# INPUT_Module.net
KiCad netlist of a schematic drawn in Altium Designer
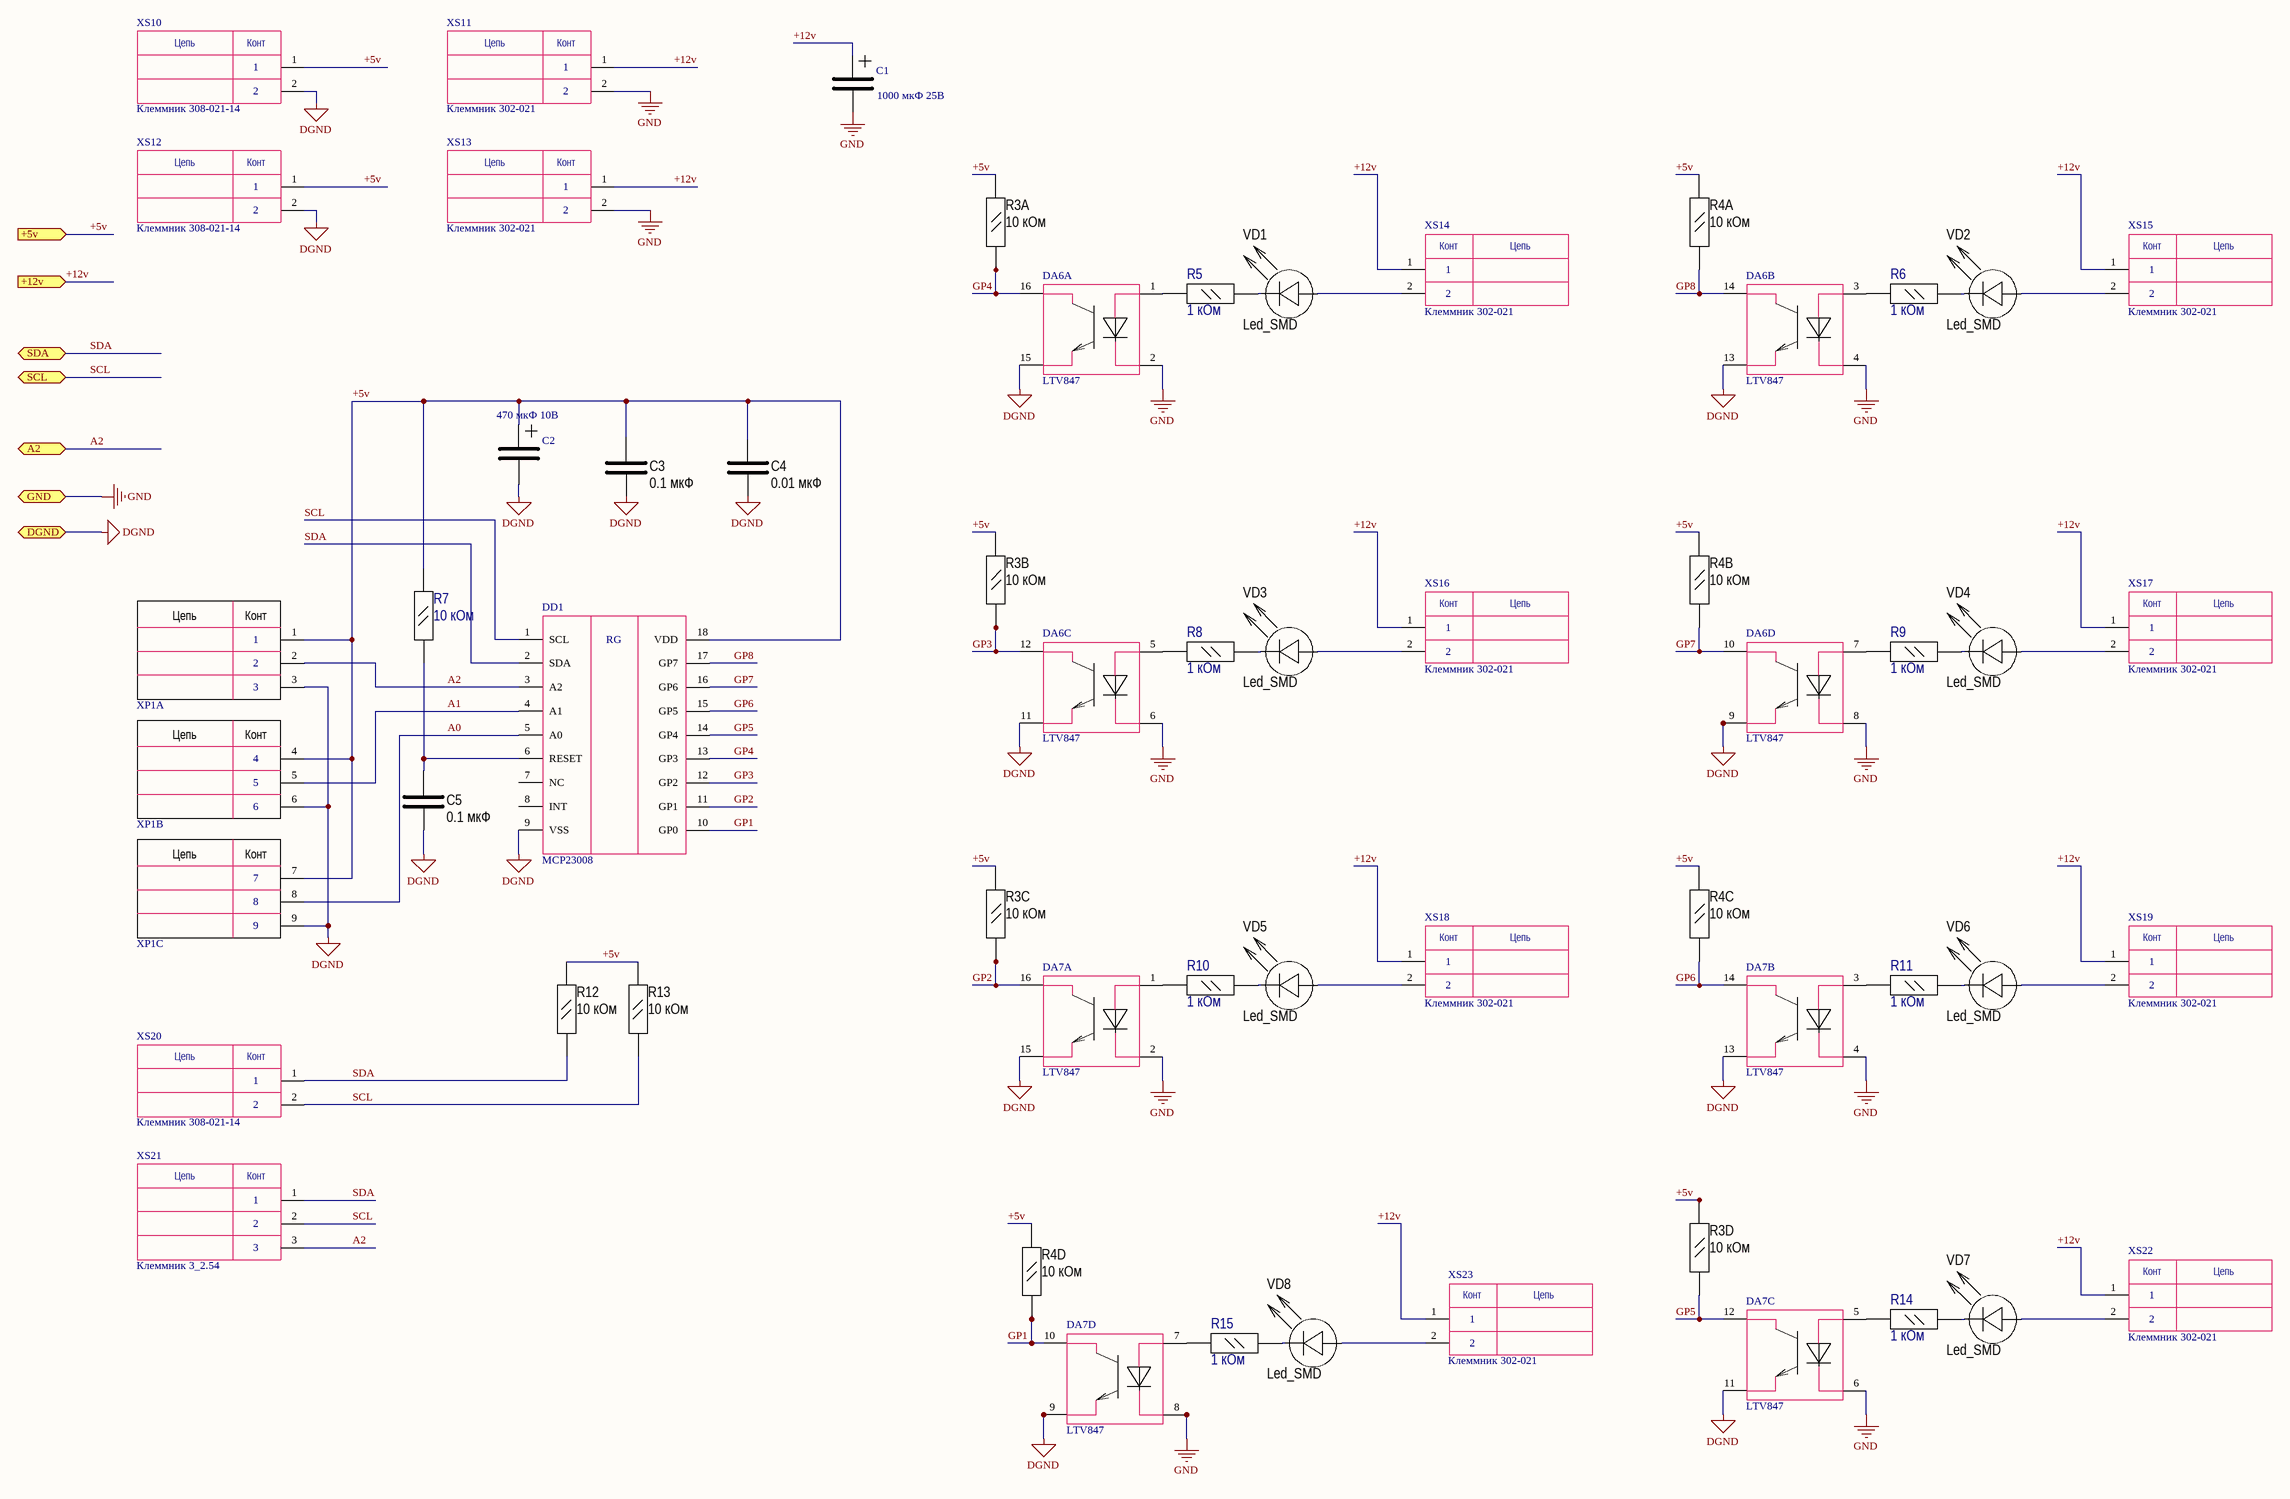
[diagram p0: INPUT_Module.SchDoc]

(export (version "E")
  (design (tool "Eeschema 10.0.6"))
  (components
    (comp (ref "C1")
      (value "1000 мкФ 25В")
      (footprint "K50-35_10mm")
      (libsource (lib "Capicator") (part "K50-35_10mm"))
    )
    (comp (ref "C2")
      (value "470 мкФ 10В")
      (footprint "K50-35_6.3mm")
      (libsource (lib "Capicator") (part "K50-35_6.3mm"))
    )
    (comp (ref "C3") (value "0.1 мкФ") (footprint "C0603") (libsource (lib "Capicator") (part "Cap_SMD")))
    (comp (ref "C4") (value "0.01 мкФ") (footprint "C0603") (libsource (lib "Capicator") (part "C0603")))
    (comp (ref "C5") (value "0.1 мкФ") (footprint "C0603") (libsource (lib "Capicator") (part "Cap_SMD")))
    (comp (ref "DA6") (value "LTV847") (footprint "DIP16") (libsource (lib "OptoRelay") (part "LTV847")))
    (comp (ref "DA7") (value "LTV847") (footprint "DIP16") (libsource (lib "OptoRelay") (part "LTV847")))
    (comp (ref "DD1")
      (value "MCP23008")
      (footprint "SOIC18")
      (libsource (lib "Микросхемы импортные") (part "MCP23008"))
    )
    (comp (ref "R3") (value "10 кОм") (footprint "CAT16_F4") (libsource (lib "Resistor") (part "KAT16-F4")))
    (comp (ref "R4") (value "10 кОм") (footprint "CAT16_F4") (libsource (lib "Resistor") (part "KAT16-F4")))
    (comp (ref "R5") (value "1 кОм") (footprint "R0805") (libsource (lib "Resistor") (part "ResSMD")))
    (comp (ref "R6") (value "1 кОм") (footprint "R0805") (libsource (lib "Resistor") (part "ResSMD")))
    (comp (ref "R7") (value "10 кОм") (footprint "R0603") (libsource (lib "") (part "ResSMD_1")))
    (comp (ref "R8") (value "1 кОм") (footprint "R0805") (libsource (lib "Resistor") (part "ResSMD")))
    (comp (ref "R9") (value "1 кОм") (footprint "R0805") (libsource (lib "Resistor") (part "ResSMD")))
    (comp (ref "R10") (value "1 кОм") (footprint "R0805") (libsource (lib "Resistor") (part "ResSMD")))
    (comp (ref "R11") (value "1 кОм") (footprint "R0805") (libsource (lib "Resistor") (part "ResSMD")))
    (comp (ref "R12") (value "10 кОм") (footprint "R0805") (libsource (lib "Resistor") (part "R0805")))
    (comp (ref "R13") (value "10 кОм") (footprint "R0805") (libsource (lib "Resistor") (part "R0805")))
    (comp (ref "R14") (value "1 кОм") (footprint "R0805") (libsource (lib "Resistor") (part "ResSMD")))
    (comp (ref "R15") (value "1 кОм") (footprint "R0805") (libsource (lib "Resistor") (part "ResSMD")))
    (comp (ref "VD1") (value "Led_SMD") (footprint "Led0805") (libsource (lib "Светодиоды") (part "Led_SMD")))
    (comp (ref "VD2") (value "Led_SMD") (footprint "Led0805") (libsource (lib "Светодиоды") (part "Led_SMD")))
    (comp (ref "VD3") (value "Led_SMD") (footprint "Led0805") (libsource (lib "Светодиоды") (part "Led_SMD")))
    (comp (ref "VD4") (value "Led_SMD") (footprint "Led0805") (libsource (lib "Светодиоды") (part "Led_SMD")))
    (comp (ref "VD5") (value "Led_SMD") (footprint "Led0805") (libsource (lib "Светодиоды") (part "Led_SMD")))
    (comp (ref "VD6") (value "Led_SMD") (footprint "Led0805") (libsource (lib "Светодиоды") (part "Led_SMD")))
    (comp (ref "VD7") (value "Led_SMD") (footprint "Led0805") (libsource (lib "Светодиоды") (part "Led_SMD")))
    (comp (ref "VD8") (value "Led_SMD") (footprint "Led0805") (libsource (lib "Светодиоды") (part "Led_SMD")))
    (comp (ref "XP1")
      (value "PLS-3*3")
      (footprint "PLS-3*3")
      (libsource (lib "Разъемы импортные") (part "PLS-3*3"))
    )
    (comp (ref "XS10")
      (value "Клеммник 308-021-14")
      (footprint "308-021-14_2.54")
      (description "308-021-14_2.54")
      (libsource (lib "Клемники") (part "Клеммник 308-021-14"))
    )
    (comp (ref "XS11")
      (value "Клеммник 302-021")
      (footprint "301-012")
      (description "302-021-xx")
      (libsource (lib "Клемники") (part "Клеммник 302-021"))
    )
    (comp (ref "XS12")
      (value "Клеммник 308-021-14")
      (footprint "308-021-14_2.54")
      (description "308-021-14_2.54")
      (libsource (lib "Клемники") (part "Клеммник 308-021-14"))
    )
    (comp (ref "XS13")
      (value "Клеммник 302-021")
      (footprint "301-012")
      (description "302-021-xx")
      (libsource (lib "Клемники") (part "Клеммник 302-021"))
    )
    (comp (ref "XS14")
      (value "Клеммник 302-021")
      (footprint "301-012")
      (description "302-021-xx")
      (libsource (lib "Клемники") (part "Клеммник 302-021"))
    )
    (comp (ref "XS15")
      (value "Клеммник 302-021")
      (footprint "301-012")
      (description "302-021-xx")
      (libsource (lib "Клемники") (part "Клеммник 302-021"))
    )
    (comp (ref "XS16")
      (value "Клеммник 302-021")
      (footprint "301-012")
      (description "302-021-xx")
      (libsource (lib "Клемники") (part "Клеммник 302-021"))
    )
    (comp (ref "XS17")
      (value "Клеммник 302-021")
      (footprint "301-012")
      (description "302-021-xx")
      (libsource (lib "Клемники") (part "Клеммник 302-021"))
    )
    (comp (ref "XS18")
      (value "Клеммник 302-021")
      (footprint "301-012")
      (description "302-021-xx")
      (libsource (lib "Клемники") (part "Клеммник 302-021"))
    )
    (comp (ref "XS19")
      (value "Клеммник 302-021")
      (footprint "301-012")
      (description "302-021-xx")
      (libsource (lib "Клемники") (part "Клеммник 302-021"))
    )
    (comp (ref "XS20")
      (value "Клеммник 308-021-14")
      (footprint "308-021-14_2.54")
      (description "308-021-14_2.54")
      (libsource (lib "Клемники") (part "Клеммник 308-021-14"))
    )
    (comp (ref "XS21")
      (value "Клеммник 3_2.54")
      (footprint "3x2_54")
      (libsource (lib "Клемники") (part "Клеммник 3_2.54"))
    )
    (comp (ref "XS22")
      (value "Клеммник 302-021")
      (footprint "301-012")
      (description "302-021-xx")
      (libsource (lib "Клемники") (part "Клеммник 302-021"))
    )
    (comp (ref "XS23")
      (value "Клеммник 302-021")
      (footprint "301-012")
      (description "302-021-xx")
      (libsource (lib "Клемники") (part "Клеммник 302-021"))
    )
  )
  (nets
    (net (code "1") (name "/+5v") (class "Default")
      (node (ref "C2") (pin "1") (pinfunction "1_1") (pintype "passive"))
      (node (ref "C3") (pin "1") (pinfunction "1_1") (pintype "passive"))
      (node (ref "C4") (pin "1") (pinfunction "1_1") (pintype "passive"))
      (node (ref "DD1") (pin "18") (pinfunction "VDD_18") (pintype "passive"))
      (node (ref "R12") (pin "1") (pinfunction "1_1") (pintype "passive"))
      (node (ref "R13") (pin "1") (pinfunction "1_1") (pintype "passive"))
      (node (ref "R3") (pin "2") (pinfunction "2_2") (pintype "passive"))
      (node (ref "R3") (pin "4") (pinfunction "4_4") (pintype "passive"))
      (node (ref "R3") (pin "6") (pinfunction "6_6") (pintype "passive"))
      (node (ref "R3") (pin "8") (pinfunction "8_8") (pintype "passive"))
      (node (ref "R4") (pin "2") (pinfunction "2_2") (pintype "passive"))
      (node (ref "R4") (pin "4") (pinfunction "4_4") (pintype "passive"))
      (node (ref "R4") (pin "6") (pinfunction "6_6") (pintype "passive"))
      (node (ref "R4") (pin "8") (pinfunction "8_8") (pintype "passive"))
      (node (ref "R7") (pin "1") (pinfunction "1_1") (pintype "passive"))
      (node (ref "XP1") (pin "1") (pintype "passive"))
      (node (ref "XP1") (pin "4") (pintype "passive"))
      (node (ref "XP1") (pin "7") (pintype "passive"))
      (node (ref "XS10") (pin "1") (pinfunction "1_1") (pintype "passive"))
      (node (ref "XS12") (pin "1") (pinfunction "1_1") (pintype "passive"))
    )
    (net (code "2") (name "/+12v") (class "Default")
      (node (ref "C1") (pin "1") (pinfunction "1_1") (pintype "passive"))
      (node (ref "XS11") (pin "1") (pinfunction "1_1") (pintype "passive"))
      (node (ref "XS13") (pin "1") (pinfunction "1_1") (pintype "passive"))
      (node (ref "XS14") (pin "1") (pinfunction "1_1") (pintype "passive"))
      (node (ref "XS15") (pin "1") (pinfunction "1_1") (pintype "passive"))
      (node (ref "XS16") (pin "1") (pinfunction "1_1") (pintype "passive"))
      (node (ref "XS17") (pin "1") (pinfunction "1_1") (pintype "passive"))
      (node (ref "XS18") (pin "1") (pinfunction "1_1") (pintype "passive"))
      (node (ref "XS19") (pin "1") (pinfunction "1_1") (pintype "passive"))
      (node (ref "XS22") (pin "1") (pinfunction "1_1") (pintype "passive"))
      (node (ref "XS23") (pin "1") (pinfunction "1_1") (pintype "passive"))
    )
    (net (code "3") (name "/A0") (class "Default")
      (node (ref "DD1") (pin "5") (pinfunction "A0_5") (pintype "passive"))
      (node (ref "XP1") (pin "8") (pintype "passive"))
    )
    (net (code "4") (name "/A1") (class "Default")
      (node (ref "DD1") (pin "4") (pinfunction "A1_4") (pintype "passive"))
      (node (ref "XP1") (pin "5") (pintype "passive"))
    )
    (net (code "5") (name "/A2") (class "Default")
      (node (ref "DD1") (pin "3") (pinfunction "A2_3") (pintype "passive"))
      (node (ref "XP1") (pin "2") (pintype "passive"))
      (node (ref "XS21") (pin "3") (pinfunction "3_3") (pintype "passive"))
    )
    (net (code "6") (name "/GP1") (class "Default")
      (node (ref "DA7") (pin "10") (pinfunction "C_10") (pintype "passive"))
      (node (ref "DD1") (pin "10") (pinfunction "GP0_10") (pintype "passive"))
      (node (ref "R4") (pin "7") (pinfunction "7_7") (pintype "passive"))
    )
    (net (code "7") (name "/GP2") (class "Default")
      (node (ref "DA7") (pin "16") (pinfunction "C_16") (pintype "passive"))
      (node (ref "DD1") (pin "11") (pinfunction "GP1_11") (pintype "passive"))
      (node (ref "R3") (pin "5") (pinfunction "5_5") (pintype "passive"))
    )
    (net (code "8") (name "/GP3") (class "Default")
      (node (ref "DA6") (pin "12") (pinfunction "C_12") (pintype "passive"))
      (node (ref "DD1") (pin "12") (pinfunction "GP2_12") (pintype "passive"))
      (node (ref "R3") (pin "3") (pinfunction "3_3") (pintype "passive"))
    )
    (net (code "9") (name "/GP4") (class "Default")
      (node (ref "DA6") (pin "16") (pinfunction "C_16") (pintype "passive"))
      (node (ref "DD1") (pin "13") (pinfunction "GP3_13") (pintype "passive"))
      (node (ref "R3") (pin "1") (pinfunction "1_1") (pintype "passive"))
    )
    (net (code "10") (name "/GP5") (class "Default")
      (node (ref "DA7") (pin "12") (pinfunction "C_12") (pintype "passive"))
      (node (ref "DD1") (pin "14") (pinfunction "GP4_14") (pintype "passive"))
      (node (ref "R3") (pin "7") (pinfunction "7_7") (pintype "passive"))
    )
    (net (code "11") (name "/GP6") (class "Default")
      (node (ref "DA7") (pin "14") (pinfunction "C_14") (pintype "passive"))
      (node (ref "DD1") (pin "15") (pinfunction "GP5_15") (pintype "passive"))
      (node (ref "R4") (pin "5") (pinfunction "5_5") (pintype "passive"))
    )
    (net (code "12") (name "/GP7") (class "Default")
      (node (ref "DA6") (pin "10") (pinfunction "C_10") (pintype "passive"))
      (node (ref "DD1") (pin "16") (pinfunction "GP6_16") (pintype "passive"))
      (node (ref "R4") (pin "3") (pinfunction "3_3") (pintype "passive"))
    )
    (net (code "13") (name "/GP8") (class "Default")
      (node (ref "DA6") (pin "14") (pinfunction "C_14") (pintype "passive"))
      (node (ref "DD1") (pin "17") (pinfunction "GP7_17") (pintype "passive"))
      (node (ref "R4") (pin "1") (pinfunction "1_1") (pintype "passive"))
    )
    (net (code "14") (name "/SCL") (class "Default")
      (node (ref "DD1") (pin "1") (pinfunction "SCL_1") (pintype "passive"))
      (node (ref "R13") (pin "2") (pinfunction "2_2") (pintype "passive"))
      (node (ref "XS20") (pin "2") (pinfunction "2_2") (pintype "passive"))
      (node (ref "XS21") (pin "2") (pinfunction "2_2") (pintype "passive"))
    )
    (net (code "15") (name "/SDA") (class "Default")
      (node (ref "DD1") (pin "2") (pinfunction "SDA_2") (pintype "passive"))
      (node (ref "R12") (pin "2") (pinfunction "2_2") (pintype "passive"))
      (node (ref "XS20") (pin "1") (pinfunction "1_1") (pintype "passive"))
      (node (ref "XS21") (pin "1") (pinfunction "1_1") (pintype "passive"))
    )
    (net (code "16") (name "DGND") (class "Default")
      (node (ref "C2") (pin "2") (pinfunction "2_2") (pintype "passive"))
      (node (ref "C3") (pin "2") (pinfunction "2_2") (pintype "passive"))
      (node (ref "C4") (pin "2") (pinfunction "2_2") (pintype "passive"))
      (node (ref "C5") (pin "2") (pinfunction "2_2") (pintype "passive"))
      (node (ref "DA6") (pin "11") (pinfunction "E_11") (pintype "passive"))
      (node (ref "DA6") (pin "13") (pinfunction "E_13") (pintype "passive"))
      (node (ref "DA6") (pin "15") (pinfunction "E_15") (pintype "passive"))
      (node (ref "DA6") (pin "9") (pinfunction "E_9") (pintype "passive"))
      (node (ref "DA7") (pin "11") (pinfunction "E_11") (pintype "passive"))
      (node (ref "DA7") (pin "13") (pinfunction "E_13") (pintype "passive"))
      (node (ref "DA7") (pin "15") (pinfunction "E_15") (pintype "passive"))
      (node (ref "DA7") (pin "9") (pinfunction "E_9") (pintype "passive"))
      (node (ref "DD1") (pin "9") (pinfunction "VSS_9") (pintype "passive"))
      (node (ref "XP1") (pin "3") (pintype "passive"))
      (node (ref "XP1") (pin "6") (pintype "passive"))
      (node (ref "XP1") (pin "9") (pintype "passive"))
      (node (ref "XS10") (pin "2") (pinfunction "2_2") (pintype "passive"))
      (node (ref "XS12") (pin "2") (pinfunction "2_2") (pintype "passive"))
    )
    (net (code "17") (name "GND") (class "Default")
      (node (ref "C1") (pin "2") (pinfunction "2_2") (pintype "passive"))
      (node (ref "DA6") (pin "2") (pinfunction "-_2") (pintype "passive"))
      (node (ref "DA6") (pin "4") (pinfunction "-_4") (pintype "passive"))
      (node (ref "DA6") (pin "6") (pinfunction "-_6") (pintype "passive"))
      (node (ref "DA6") (pin "8") (pinfunction "-_8") (pintype "passive"))
      (node (ref "DA7") (pin "2") (pinfunction "-_2") (pintype "passive"))
      (node (ref "DA7") (pin "4") (pinfunction "-_4") (pintype "passive"))
      (node (ref "DA7") (pin "6") (pinfunction "-_6") (pintype "passive"))
      (node (ref "DA7") (pin "8") (pinfunction "-_8") (pintype "passive"))
      (node (ref "XS11") (pin "2") (pinfunction "2_2") (pintype "passive"))
      (node (ref "XS13") (pin "2") (pinfunction "2_2") (pintype "passive"))
    )
    (net (code "18") (name "Net-(DA6A-+)") (class "Default")
      (node (ref "DA6") (pin "1") (pinfunction "+_1") (pintype "passive"))
      (node (ref "R5") (pin "2") (pinfunction "2_2") (pintype "passive"))
    )
    (net (code "19") (name "Net-(DA6B-+)") (class "Default")
      (node (ref "DA6") (pin "3") (pinfunction "+_3") (pintype "passive"))
      (node (ref "R6") (pin "2") (pinfunction "2_2") (pintype "passive"))
    )
    (net (code "20") (name "Net-(DA6C-+)") (class "Default")
      (node (ref "DA6") (pin "5") (pinfunction "+_5") (pintype "passive"))
      (node (ref "R8") (pin "2") (pinfunction "2_2") (pintype "passive"))
    )
    (net (code "21") (name "Net-(DA6D-+)") (class "Default")
      (node (ref "DA6") (pin "7") (pinfunction "+_7") (pintype "passive"))
      (node (ref "R9") (pin "2") (pinfunction "2_2") (pintype "passive"))
    )
    (net (code "22") (name "Net-(DA7A-+)") (class "Default")
      (node (ref "DA7") (pin "1") (pinfunction "+_1") (pintype "passive"))
      (node (ref "R10") (pin "2") (pinfunction "2_2") (pintype "passive"))
    )
    (net (code "23") (name "Net-(DA7B-+)") (class "Default")
      (node (ref "DA7") (pin "3") (pinfunction "+_3") (pintype "passive"))
      (node (ref "R11") (pin "2") (pinfunction "2_2") (pintype "passive"))
    )
    (net (code "24") (name "Net-(DA7C-+)") (class "Default")
      (node (ref "DA7") (pin "5") (pinfunction "+_5") (pintype "passive"))
      (node (ref "R14") (pin "2") (pinfunction "2_2") (pintype "passive"))
    )
    (net (code "25") (name "Net-(DA7D-+)") (class "Default")
      (node (ref "DA7") (pin "7") (pinfunction "+_7") (pintype "passive"))
      (node (ref "R15") (pin "2") (pinfunction "2_2") (pintype "passive"))
    )
    (net (code "26") (name "Net-(DD1-RESET)") (class "Default")
      (node (ref "C5") (pin "1") (pinfunction "1_1") (pintype "passive"))
      (node (ref "DD1") (pin "6") (pinfunction "RESET_6") (pintype "passive"))
      (node (ref "R7") (pin "2") (pinfunction "2_2") (pintype "passive"))
    )
    (net (code "27") (name "Net-(R5-Pad1)") (class "Default")
      (node (ref "R5") (pin "1") (pinfunction "1_1") (pintype "passive"))
      (node (ref "VD1") (pin "1") (pinfunction "1_1") (pintype "passive"))
    )
    (net (code "28") (name "Net-(R6-Pad1)") (class "Default")
      (node (ref "R6") (pin "1") (pinfunction "1_1") (pintype "passive"))
      (node (ref "VD2") (pin "1") (pinfunction "1_1") (pintype "passive"))
    )
    (net (code "29") (name "Net-(R8-Pad1)") (class "Default")
      (node (ref "R8") (pin "1") (pinfunction "1_1") (pintype "passive"))
      (node (ref "VD3") (pin "1") (pinfunction "1_1") (pintype "passive"))
    )
    (net (code "30") (name "Net-(R9-Pad1)") (class "Default")
      (node (ref "R9") (pin "1") (pinfunction "1_1") (pintype "passive"))
      (node (ref "VD4") (pin "1") (pinfunction "1_1") (pintype "passive"))
    )
    (net (code "31") (name "Net-(R10-Pad1)") (class "Default")
      (node (ref "R10") (pin "1") (pinfunction "1_1") (pintype "passive"))
      (node (ref "VD5") (pin "1") (pinfunction "1_1") (pintype "passive"))
    )
    (net (code "32") (name "Net-(R11-Pad1)") (class "Default")
      (node (ref "R11") (pin "1") (pinfunction "1_1") (pintype "passive"))
      (node (ref "VD6") (pin "1") (pinfunction "1_1") (pintype "passive"))
    )
    (net (code "33") (name "Net-(R14-Pad1)") (class "Default")
      (node (ref "R14") (pin "1") (pinfunction "1_1") (pintype "passive"))
      (node (ref "VD7") (pin "1") (pinfunction "1_1") (pintype "passive"))
    )
    (net (code "34") (name "Net-(R15-Pad1)") (class "Default")
      (node (ref "R15") (pin "1") (pinfunction "1_1") (pintype "passive"))
      (node (ref "VD8") (pin "1") (pinfunction "1_1") (pintype "passive"))
    )
    (net (code "35") (name "Net-(VD1-Pad2)") (class "Default")
      (node (ref "VD1") (pin "2") (pinfunction "2_2") (pintype "passive"))
      (node (ref "XS14") (pin "2") (pinfunction "2_2") (pintype "passive"))
    )
    (net (code "36") (name "Net-(VD2-Pad2)") (class "Default")
      (node (ref "VD2") (pin "2") (pinfunction "2_2") (pintype "passive"))
      (node (ref "XS15") (pin "2") (pinfunction "2_2") (pintype "passive"))
    )
    (net (code "37") (name "Net-(VD3-Pad2)") (class "Default")
      (node (ref "VD3") (pin "2") (pinfunction "2_2") (pintype "passive"))
      (node (ref "XS16") (pin "2") (pinfunction "2_2") (pintype "passive"))
    )
    (net (code "38") (name "Net-(VD4-Pad2)") (class "Default")
      (node (ref "VD4") (pin "2") (pinfunction "2_2") (pintype "passive"))
      (node (ref "XS17") (pin "2") (pinfunction "2_2") (pintype "passive"))
    )
    (net (code "39") (name "Net-(VD5-Pad2)") (class "Default")
      (node (ref "VD5") (pin "2") (pinfunction "2_2") (pintype "passive"))
      (node (ref "XS18") (pin "2") (pinfunction "2_2") (pintype "passive"))
    )
    (net (code "40") (name "Net-(VD6-Pad2)") (class "Default")
      (node (ref "VD6") (pin "2") (pinfunction "2_2") (pintype "passive"))
      (node (ref "XS19") (pin "2") (pinfunction "2_2") (pintype "passive"))
    )
    (net (code "41") (name "Net-(VD7-Pad2)") (class "Default")
      (node (ref "VD7") (pin "2") (pinfunction "2_2") (pintype "passive"))
      (node (ref "XS22") (pin "2") (pinfunction "2_2") (pintype "passive"))
    )
    (net (code "42") (name "Net-(VD8-Pad2)") (class "Default")
      (node (ref "VD8") (pin "2") (pinfunction "2_2") (pintype "passive"))
      (node (ref "XS23") (pin "2") (pinfunction "2_2") (pintype "passive"))
    )
    (net (code "43") (name "unconnected-(DD1-INT-Pad8)") (class "Default")
      (node (ref "DD1") (pin "8") (pinfunction "INT_8") (pintype "passive"))
    )
    (net (code "44") (name "unconnected-(DD1-NC-Pad7)") (class "Default")
      (node (ref "DD1") (pin "7") (pinfunction "NC_7") (pintype "passive"))
    )
  )
)
